# prototype.net
KiCad netlist of a schematic drawn in Altium Designer
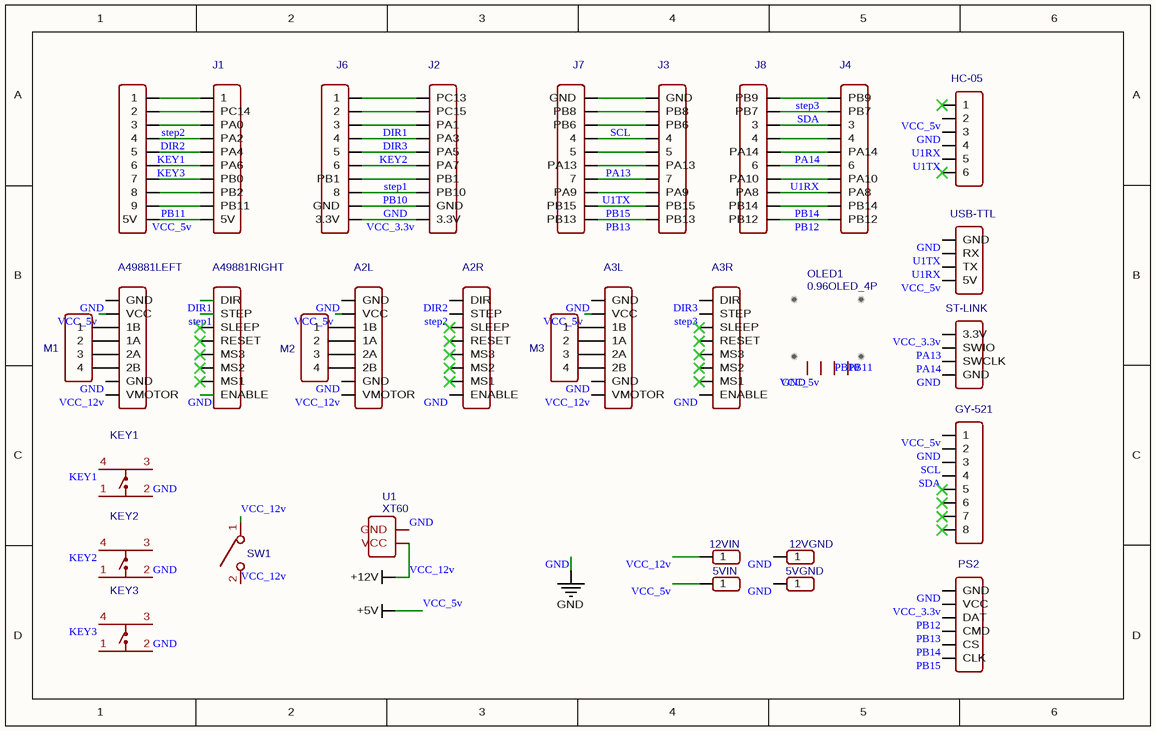
[diagram p0: prototype.schdoc]

(export (version "E")
  (design (tool "Eeschema 10.0.6"))
  (components
    (comp (ref "5VGND")
      (value "HDR-M-2.54_1x1")
      (fields (field (name "BOM_SUPPLIER PART") "C81276") (field (name "CONTRIBUTOR") "LCEDA_Lib"))
      (libsource (lib "altium-import") (part "root_0_HDR-M-2.54_1x1_"))
    )
    (comp (ref "5VIN")
      (value "HDR-M-2.54_1x1")
      (fields (field (name "BOM_SUPPLIER PART") "C81276") (field (name "CONTRIBUTOR") "LCEDA_Lib"))
      (libsource (lib "altium-import") (part "root_0_HDR-M-2.54_1x1_"))
    )
    (comp (ref "12VGND")
      (value "HDR-M-2.54_1x1")
      (fields (field (name "BOM_SUPPLIER PART") "C81276") (field (name "CONTRIBUTOR") "LCEDA_Lib"))
      (libsource (lib "altium-import") (part "root_0_HDR-M-2.54_1x1_"))
    )
    (comp (ref "12VIN")
      (value "HDR-M-2.54_1x1")
      (fields (field (name "BOM_SUPPLIER PART") "C81276") (field (name "CONTRIBUTOR") "LCEDA_Lib"))
      (libsource (lib "altium-import") (part "root_0_HDR-M-2.54_1x1_"))
    )
    (comp (ref "A2L")
      (value "HDR-M-2.54_1x8")
      (fields (field (name "BOM_SUPPLIER PART") "C190820") (field (name "CONTRIBUTOR") "LCEDA_Lib"))
      (libsource (lib "altium-import") (part "root_0_HDR-M-2.54_1x8_"))
    )
    (comp (ref "A2R")
      (value "HDR-M-2.54_1x8")
      (fields (field (name "BOM_SUPPLIER PART") "C190820") (field (name "CONTRIBUTOR") "LCEDA_Lib"))
      (libsource (lib "altium-import") (part "root_0_HDR-M-2.54_1x8_"))
    )
    (comp (ref "A3L")
      (value "HDR-M-2.54_1x8")
      (fields (field (name "BOM_SUPPLIER PART") "C190820") (field (name "CONTRIBUTOR") "LCEDA_Lib"))
      (libsource (lib "altium-import") (part "root_0_HDR-M-2.54_1x8_"))
    )
    (comp (ref "A3R")
      (value "HDR-M-2.54_1x8")
      (fields (field (name "BOM_SUPPLIER PART") "C190820") (field (name "CONTRIBUTOR") "LCEDA_Lib"))
      (libsource (lib "altium-import") (part "root_0_HDR-M-2.54_1x8_"))
    )
    (comp (ref "A49881LEFT")
      (value "HDR-M-2.54_1x8")
      (fields (field (name "BOM_SUPPLIER PART") "C190820") (field (name "CONTRIBUTOR") "LCEDA_Lib"))
      (libsource (lib "altium-import") (part "root_0_HDR-M-2.54_1x8_"))
    )
    (comp (ref "A49881RIGHT")
      (value "HDR-M-2.54_1x8")
      (fields (field (name "BOM_SUPPLIER PART") "C190820") (field (name "CONTRIBUTOR") "LCEDA_Lib"))
      (libsource (lib "altium-import") (part "root_0_HDR-M-2.54_1x8_"))
    )
    (comp (ref "GY-521")
      (value "HDR-M-2.54_1x8")
      (fields (field (name "BOM_SUPPLIER PART") "C190820") (field (name "CONTRIBUTOR") "LCEDA_Lib"))
      (libsource (lib "altium-import") (part "root_0_HDR-M-2.54_1x8_"))
    )
    (comp (ref "HC-05")
      (value "HDR-M-2.54_1x6")
      (fields (field (name "BOM_SUPPLIER PART") "C190819") (field (name "CONTRIBUTOR") "LCEDA_Lib"))
      (libsource (lib "") (part "root_2_HDR-M-2.54_1x6__1"))
    )
    (comp (ref "J1")
      (value "HDR-M-2.54_1x10")
      (fields (field (name "BOM_SUPPLIER PART") "C57369") (field (name "CONTRIBUTOR") "LCEDA_Lib"))
      (libsource (lib "altium-import") (part "root_0_HDR-M-2.54_1x10_"))
    )
    (comp (ref "J2")
      (value "HDR-M-2.54_1x10")
      (fields (field (name "BOM_SUPPLIER PART") "C57369") (field (name "CONTRIBUTOR") "LCEDA_Lib"))
      (libsource (lib "altium-import") (part "root_0_HDR-M-2.54_1x10_"))
    )
    (comp (ref "J3")
      (value "HDR-M-2.54_1x10")
      (fields (field (name "BOM_SUPPLIER PART") "C57369") (field (name "CONTRIBUTOR") "LCEDA_Lib"))
      (libsource (lib "altium-import") (part "root_0_HDR-M-2.54_1x10_"))
    )
    (comp (ref "J4")
      (value "HDR-M-2.54_1x10")
      (fields (field (name "BOM_SUPPLIER PART") "C57369") (field (name "CONTRIBUTOR") "LCEDA_Lib"))
      (libsource (lib "altium-import") (part "root_0_HDR-M-2.54_1x10_"))
    )
    (comp (ref "J5")
      (value "HDR-M-2.54_1x10")
      (fields (field (name "BOM_SUPPLIER PART") "C57369") (field (name "CONTRIBUTOR") "LCEDA_Lib"))
      (libsource (lib "altium-import") (part "root_2_HDR-M-2.54_1x10_"))
    )
    (comp (ref "J6")
      (value "HDR-M-2.54_1x10")
      (fields (field (name "BOM_SUPPLIER PART") "C57369") (field (name "CONTRIBUTOR") "LCEDA_Lib"))
      (libsource (lib "") (part "root_0_HDR-M-2.54_1x10__2"))
    )
    (comp (ref "J7")
      (value "HDR-M-2.54_1x10")
      (fields (field (name "BOM_SUPPLIER PART") "C57369") (field (name "CONTRIBUTOR") "LCEDA_Lib"))
      (libsource (lib "") (part "root_0_HDR-M-2.54_1x10__3"))
    )
    (comp (ref "J8")
      (value "HDR-M-2.54_1x10")
      (fields (field (name "BOM_SUPPLIER PART") "C57369") (field (name "CONTRIBUTOR") "LCEDA_Lib"))
      (libsource (lib "") (part "root_0_HDR-M-2.54_1x10__1"))
    )
    (comp (ref "KEY1")
      (value "KEY-6*6*9.5")
      (fields
        (field (name "BOM_SUPPLIER PART") "C22546")
        (field (name "BOM_MANUFACTURER PART") "直插轻触开关 6*6*9.5")
      )
      (libsource (lib "altium-import") (part "root_0_KEY-6*6*9.5_"))
    )
    (comp (ref "KEY2")
      (value "KEY-6*6*9.5")
      (fields
        (field (name "BOM_SUPPLIER PART") "C22546")
        (field (name "BOM_MANUFACTURER PART") "直插轻触开关 6*6*9.5")
      )
      (libsource (lib "altium-import") (part "root_0_KEY-6*6*9.5_"))
    )
    (comp (ref "KEY3")
      (value "KEY-6*6*9.5")
      (fields
        (field (name "BOM_SUPPLIER PART") "C22546")
        (field (name "BOM_MANUFACTURER PART") "直插轻触开关 6*6*9.5")
      )
      (libsource (lib "altium-import") (part "root_0_KEY-6*6*9.5_"))
    )
    (comp (ref "M1")
      (value "HDR-M-2.54_1x4")
      (fields (field (name "BOM_SUPPLIER PART") "C124378") (field (name "CONTRIBUTOR") "LCEDA_Lib"))
      (libsource (lib "") (part "root_0_HDR-M-2.54_1x4__1"))
    )
    (comp (ref "M2")
      (value "HDR-M-2.54_1x4")
      (fields (field (name "BOM_SUPPLIER PART") "C124378") (field (name "CONTRIBUTOR") "LCEDA_Lib"))
      (libsource (lib "") (part "root_0_HDR-M-2.54_1x4__1"))
    )
    (comp (ref "M3")
      (value "HDR-M-2.54_1x4")
      (fields (field (name "BOM_SUPPLIER PART") "C124378") (field (name "CONTRIBUTOR") "LCEDA_Lib"))
      (libsource (lib "") (part "root_0_HDR-M-2.54_1x4__1"))
    )
    (comp (ref "OLED1")
      (value "0.96OLED_4P")
      (fields (field (name "CONTRIBUTOR") "LCEDA_Lib"))
      (libsource (lib "altium-import") (part "root_0_0.96OLED_4P_"))
    )
    (comp (ref "PS2")
      (value "HDR-M-2.54_1x6")
      (fields (field (name "BOM_SUPPLIER PART") "C190819") (field (name "CONTRIBUTOR") "LCEDA_Lib"))
      (libsource (lib "altium-import") (part "root_2_HDR-M-2.54_1x6_"))
    )
    (comp (ref "ST-LINK")
      (value "HDR-M-2.54_1x4")
      (fields (field (name "BOM_SUPPLIER PART") "C124378") (field (name "CONTRIBUTOR") "LCEDA_Lib"))
      (libsource (lib "altium-import") (part "root_0_HDR-M-2.54_1x4_"))
    )
    (comp (ref "SW1")
      (value "小型 船型/形开关 KCD11 2档2脚 2档3脚 15*10mm 翘板开关")
      (fields
        (field (name "BOM_SUPPLIER PART") "C309064")
        (field (name "BOM_MANUFACTURER PART") "SS01-BBIWL-RP20-R")
        (field (name "CONTRIBUTOR") "CyTech")
      )
      (libsource (lib "altium-import") (part "root_1_小型 船型/形开关 KCD11 2档2脚 2档3脚 15*10mm 翘板开关_"))
    )
    (comp (ref "U1")
      (value "XT60")
      (fields (field (name "CONTRIBUTOR") "AKER"))
      (libsource (lib "altium-import") (part "root_2_XT60_"))
    )
    (comp (ref "USB-TTL")
      (value "HDR-M-2.54_1x4")
      (fields (field (name "BOM_SUPPLIER PART") "C124378") (field (name "CONTRIBUTOR") "LCEDA_Lib"))
      (libsource (lib "") (part "root_0_HDR-M-2.54_1x4__2"))
    )
  )
  (nets
    (net (code "1") (name "+5V") (class "Default")
      (node (ref "5VIN") (pin "1") (pinfunction "1_1") (pintype "passive"))
      (node (ref "A2L") (pin "2") (pinfunction "VCC_2") (pintype "passive"))
      (node (ref "A3L") (pin "2") (pinfunction "VCC_2") (pintype "passive"))
      (node (ref "A49881LEFT") (pin "2") (pinfunction "VCC_2") (pintype "passive"))
      (node (ref "GY-521") (pin "1") (pinfunction "GND_1") (pintype "passive"))
      (node (ref "HC-05") (pin "2") (pinfunction "2_2") (pintype "passive"))
      (node (ref "J1") (pin "10") (pinfunction "5V_10") (pintype "passive"))
      (node (ref "J5") (pin "10") (pinfunction "5V_10") (pintype "passive"))
      (node (ref "OLED1") (pin "2") (pinfunction "2_2") (pintype "passive"))
      (node (ref "USB-TTL") (pin "4") (pinfunction "5V_4") (pintype "passive"))
    )
    (net (code "2") (name "+12V") (class "Default")
      (node (ref "12VIN") (pin "1") (pinfunction "1_1") (pintype "passive"))
      (node (ref "A2L") (pin "8") (pinfunction "VMOTOR_8") (pintype "passive"))
      (node (ref "A3L") (pin "8") (pinfunction "VMOTOR_8") (pintype "passive"))
      (node (ref "A49881LEFT") (pin "8") (pinfunction "VMOTOR_8") (pintype "passive"))
      (node (ref "SW1") (pin "1") (pinfunction "1_1") (pintype "passive"))
      (node (ref "SW1") (pin "2") (pinfunction "2_2") (pintype "passive"))
      (node (ref "U1") (pin "1") (pinfunction "VCC_1") (pintype "passive"))
    )
    (net (code "3") (name "/DIR1") (class "Default")
      (node (ref "A49881RIGHT") (pin "1") (pinfunction "GND_1") (pintype "passive"))
      (node (ref "J2") (pin "3") (pinfunction "PA0_3") (pintype "passive"))
      (node (ref "J6") (pin "3") (pinfunction "3_3") (pintype "passive"))
    )
    (net (code "4") (name "/DIR2") (class "Default")
      (node (ref "A2R") (pin "1") (pinfunction "GND_1") (pintype "passive"))
      (node (ref "J1") (pin "4") (pinfunction "PA2_4") (pintype "passive"))
      (node (ref "J5") (pin "4") (pinfunction "4_4") (pintype "passive"))
    )
    (net (code "5") (name "/DIR3") (class "Default")
      (node (ref "A3R") (pin "1") (pinfunction "GND_1") (pintype "passive"))
      (node (ref "J2") (pin "4") (pinfunction "PA2_4") (pintype "passive"))
      (node (ref "J6") (pin "4") (pinfunction "4_4") (pintype "passive"))
    )
    (net (code "6") (name "/KEY1") (class "Default")
      (node (ref "J1") (pin "5") (pinfunction "PA4_5") (pintype "passive"))
      (node (ref "J5") (pin "5") (pinfunction "5_5") (pintype "passive"))
      (node (ref "KEY1") (pin "4") (pinfunction "4_4") (pintype "passive"))
    )
    (net (code "7") (name "/KEY2") (class "Default")
      (node (ref "J2") (pin "5") (pinfunction "PA4_5") (pintype "passive"))
      (node (ref "J6") (pin "5") (pinfunction "5_5") (pintype "passive"))
      (node (ref "KEY2") (pin "4") (pinfunction "4_4") (pintype "passive"))
    )
    (net (code "8") (name "/KEY3") (class "Default")
      (node (ref "J1") (pin "6") (pinfunction "PA6_6") (pintype "passive"))
      (node (ref "J5") (pin "6") (pinfunction "6_6") (pintype "passive"))
      (node (ref "KEY3") (pin "4") (pinfunction "4_4") (pintype "passive"))
    )
    (net (code "9") (name "/PA13") (class "Default")
      (node (ref "J3") (pin "6") (pinfunction "PA6_6") (pintype "passive"))
      (node (ref "J7") (pin "6") (pinfunction "PA13_6") (pintype "passive"))
      (node (ref "ST-LINK") (pin "2") (pinfunction "SWIO_2") (pintype "passive"))
    )
    (net (code "10") (name "/PA14") (class "Default")
      (node (ref "J4") (pin "5") (pinfunction "PA4_5") (pintype "passive"))
      (node (ref "J8") (pin "5") (pinfunction "PA14_5") (pintype "passive"))
      (node (ref "ST-LINK") (pin "3") (pinfunction "SWCLK_3") (pintype "passive"))
    )
    (net (code "11") (name "/PB10") (class "Default")
      (node (ref "J2") (pin "8") (pinfunction "PB2_8") (pintype "passive"))
      (node (ref "J6") (pin "8") (pinfunction "8_8") (pintype "passive"))
      (node (ref "OLED1") (pin "3") (pinfunction "3_3") (pintype "passive"))
    )
    (net (code "12") (name "/PB11") (class "Default")
      (node (ref "J1") (pin "9") (pinfunction "PB11_9") (pintype "passive"))
      (node (ref "J5") (pin "9") (pinfunction "9_9") (pintype "passive"))
      (node (ref "OLED1") (pin "4") (pinfunction "4_4") (pintype "passive"))
    )
    (net (code "13") (name "/PB12") (class "Default")
      (node (ref "J4") (pin "10") (pinfunction "5V_10") (pintype "passive"))
      (node (ref "J8") (pin "10") (pinfunction "PB12_10") (pintype "passive"))
      (node (ref "PS2") (pin "4") (pinfunction "DAT_4") (pintype "passive"))
    )
    (net (code "14") (name "/PB13") (class "Default")
      (node (ref "J3") (pin "10") (pinfunction "5V_10") (pintype "passive"))
      (node (ref "J7") (pin "10") (pinfunction "PB13_10") (pintype "passive"))
      (node (ref "PS2") (pin "3") (pinfunction "CMD_3") (pintype "passive"))
    )
    (net (code "15") (name "/PB14") (class "Default")
      (node (ref "J4") (pin "9") (pinfunction "PB11_9") (pintype "passive"))
      (node (ref "J8") (pin "9") (pinfunction "PB14_9") (pintype "passive"))
      (node (ref "PS2") (pin "2") (pinfunction "CS_2") (pintype "passive"))
    )
    (net (code "16") (name "/PB15") (class "Default")
      (node (ref "J3") (pin "9") (pinfunction "PB11_9") (pintype "passive"))
      (node (ref "J7") (pin "9") (pinfunction "PB15_9") (pintype "passive"))
      (node (ref "PS2") (pin "1") (pinfunction "CLK_1") (pintype "passive"))
    )
    (net (code "17") (name "/SCL") (class "Default")
      (node (ref "GY-521") (pin "3") (pinfunction "1B_3") (pintype "passive"))
      (node (ref "J3") (pin "3") (pinfunction "PA0_3") (pintype "passive"))
      (node (ref "J7") (pin "3") (pinfunction "PB6_3") (pintype "passive"))
    )
    (net (code "18") (name "/SDA") (class "Default")
      (node (ref "GY-521") (pin "4") (pinfunction "1A_4") (pintype "passive"))
      (node (ref "J4") (pin "2") (pinfunction "PC14_2") (pintype "passive"))
      (node (ref "J8") (pin "2") (pinfunction "PB7_2") (pintype "passive"))
    )
    (net (code "19") (name "/U1RX") (class "Default")
      (node (ref "HC-05") (pin "4") (pinfunction "4_4") (pintype "passive"))
      (node (ref "J4") (pin "7") (pinfunction "PB0_7") (pintype "passive"))
      (node (ref "J8") (pin "7") (pinfunction "PA10_7") (pintype "passive"))
      (node (ref "USB-TTL") (pin "3") (pinfunction "TX_3") (pintype "passive"))
    )
    (net (code "20") (name "/U1TX") (class "Default")
      (node (ref "HC-05") (pin "5") (pinfunction "5_5") (pintype "passive"))
      (node (ref "J3") (pin "8") (pinfunction "PB2_8") (pintype "passive"))
      (node (ref "J7") (pin "8") (pinfunction "PA9_8") (pintype "passive"))
      (node (ref "USB-TTL") (pin "2") (pinfunction "RX_2") (pintype "passive"))
    )
    (net (code "21") (name "/VCC_3.3v") (class "Default")
      (node (ref "J2") (pin "10") (pinfunction "5V_10") (pintype "passive"))
      (node (ref "J6") (pin "10") (pinfunction "3.3V_10") (pintype "passive"))
      (node (ref "PS2") (pin "5") (pinfunction "VCC_5") (pintype "passive"))
      (node (ref "ST-LINK") (pin "1") (pinfunction "3.3V_1") (pintype "passive"))
    )
    (net (code "22") (name "/step1") (class "Default")
      (node (ref "A49881RIGHT") (pin "2") (pinfunction "VCC_2") (pintype "passive"))
      (node (ref "J2") (pin "7") (pinfunction "PB0_7") (pintype "passive"))
      (node (ref "J6") (pin "7") (pinfunction "PB1_7") (pintype "passive"))
    )
    (net (code "23") (name "/step2") (class "Default")
      (node (ref "A2R") (pin "2") (pinfunction "VCC_2") (pintype "passive"))
      (node (ref "J1") (pin "3") (pinfunction "PA0_3") (pintype "passive"))
      (node (ref "J5") (pin "3") (pinfunction "3_3") (pintype "passive"))
    )
    (net (code "24") (name "/step3") (class "Default")
      (node (ref "A3R") (pin "2") (pinfunction "VCC_2") (pintype "passive"))
      (node (ref "J4") (pin "1") (pinfunction "1_1") (pintype "passive"))
      (node (ref "J8") (pin "1") (pinfunction "PB9_1") (pintype "passive"))
    )
    (net (code "25") (name "GND") (class "Default")
      (node (ref "12VGND") (pin "1") (pinfunction "1_1") (pintype "passive"))
      (node (ref "5VGND") (pin "1") (pinfunction "1_1") (pintype "passive"))
      (node (ref "A2L") (pin "1") (pinfunction "GND_1") (pintype "passive"))
      (node (ref "A2L") (pin "7") (pinfunction "GND_7") (pintype "passive"))
      (node (ref "A2R") (pin "8") (pinfunction "VMOTOR_8") (pintype "passive"))
      (node (ref "A3L") (pin "1") (pinfunction "GND_1") (pintype "passive"))
      (node (ref "A3L") (pin "7") (pinfunction "GND_7") (pintype "passive"))
      (node (ref "A3R") (pin "8") (pinfunction "VMOTOR_8") (pintype "passive"))
      (node (ref "A49881LEFT") (pin "1") (pinfunction "GND_1") (pintype "passive"))
      (node (ref "A49881LEFT") (pin "7") (pinfunction "GND_7") (pintype "passive"))
      (node (ref "A49881RIGHT") (pin "8") (pinfunction "VMOTOR_8") (pintype "passive"))
      (node (ref "GY-521") (pin "2") (pinfunction "VCC_2") (pintype "passive"))
      (node (ref "HC-05") (pin "3") (pinfunction "3_3") (pintype "passive"))
      (node (ref "J2") (pin "9") (pinfunction "PB11_9") (pintype "passive"))
      (node (ref "J6") (pin "9") (pinfunction "GND_9") (pintype "passive"))
      (node (ref "KEY1") (pin "2") (pinfunction "2_2") (pintype "passive"))
      (node (ref "KEY2") (pin "2") (pinfunction "2_2") (pintype "passive"))
      (node (ref "KEY3") (pin "2") (pinfunction "2_2") (pintype "passive"))
      (node (ref "OLED1") (pin "1") (pinfunction "1_1") (pintype "passive"))
      (node (ref "PS2") (pin "6") (pinfunction "GND_6") (pintype "passive"))
      (node (ref "ST-LINK") (pin "4") (pinfunction "GND_4") (pintype "passive"))
      (node (ref "U1") (pin "2") (pinfunction "GND_2") (pintype "passive"))
      (node (ref "USB-TTL") (pin "1") (pinfunction "GND_1") (pintype "passive"))
    )
    (net (code "26") (name "Net-(A2L-1A)") (class "Default")
      (node (ref "A2L") (pin "4") (pinfunction "1A_4") (pintype "passive"))
      (node (ref "M2") (pin "2") (pinfunction "2_2") (pintype "passive"))
    )
    (net (code "27") (name "Net-(A2L-1B)") (class "Default")
      (node (ref "A2L") (pin "3") (pinfunction "1B_3") (pintype "passive"))
      (node (ref "M2") (pin "1") (pinfunction "1_1") (pintype "passive"))
    )
    (net (code "28") (name "Net-(A2L-2A)") (class "Default")
      (node (ref "A2L") (pin "5") (pinfunction "2A_5") (pintype "passive"))
      (node (ref "M2") (pin "3") (pinfunction "3_3") (pintype "passive"))
    )
    (net (code "29") (name "Net-(A2L-2B)") (class "Default")
      (node (ref "A2L") (pin "6") (pinfunction "2B_6") (pintype "passive"))
      (node (ref "M2") (pin "4") (pinfunction "4_4") (pintype "passive"))
    )
    (net (code "30") (name "Net-(A3L-1A)") (class "Default")
      (node (ref "A3L") (pin "4") (pinfunction "1A_4") (pintype "passive"))
      (node (ref "M3") (pin "2") (pinfunction "2_2") (pintype "passive"))
    )
    (net (code "31") (name "Net-(A3L-1B)") (class "Default")
      (node (ref "A3L") (pin "3") (pinfunction "1B_3") (pintype "passive"))
      (node (ref "M3") (pin "1") (pinfunction "1_1") (pintype "passive"))
    )
    (net (code "32") (name "Net-(A3L-2A)") (class "Default")
      (node (ref "A3L") (pin "5") (pinfunction "2A_5") (pintype "passive"))
      (node (ref "M3") (pin "3") (pinfunction "3_3") (pintype "passive"))
    )
    (net (code "33") (name "Net-(A3L-2B)") (class "Default")
      (node (ref "A3L") (pin "6") (pinfunction "2B_6") (pintype "passive"))
      (node (ref "M3") (pin "4") (pinfunction "4_4") (pintype "passive"))
    )
    (net (code "34") (name "Net-(A49881LEFT-1A)") (class "Default")
      (node (ref "A49881LEFT") (pin "4") (pinfunction "1A_4") (pintype "passive"))
      (node (ref "M1") (pin "2") (pinfunction "2_2") (pintype "passive"))
    )
    (net (code "35") (name "Net-(A49881LEFT-1B)") (class "Default")
      (node (ref "A49881LEFT") (pin "3") (pinfunction "1B_3") (pintype "passive"))
      (node (ref "M1") (pin "1") (pinfunction "1_1") (pintype "passive"))
    )
    (net (code "36") (name "Net-(A49881LEFT-2A)") (class "Default")
      (node (ref "A49881LEFT") (pin "5") (pinfunction "2A_5") (pintype "passive"))
      (node (ref "M1") (pin "3") (pinfunction "3_3") (pintype "passive"))
    )
    (net (code "37") (name "Net-(A49881LEFT-2B)") (class "Default")
      (node (ref "A49881LEFT") (pin "6") (pinfunction "2B_6") (pintype "passive"))
      (node (ref "M1") (pin "4") (pinfunction "4_4") (pintype "passive"))
    )
    (net (code "38") (name "Net-(J1-PB0)") (class "Default")
      (node (ref "J1") (pin "7") (pinfunction "PB0_7") (pintype "passive"))
      (node (ref "J5") (pin "7") (pinfunction "7_7") (pintype "passive"))
    )
    (net (code "39") (name "Net-(J1-PB2)") (class "Default")
      (node (ref "J1") (pin "8") (pinfunction "PB2_8") (pintype "passive"))
      (node (ref "J5") (pin "8") (pinfunction "8_8") (pintype "passive"))
    )
    (net (code "40") (name "Net-(J1-PC14)") (class "Default")
      (node (ref "J1") (pin "2") (pinfunction "PC14_2") (pintype "passive"))
      (node (ref "J5") (pin "2") (pinfunction "2_2") (pintype "passive"))
    )
    (net (code "41") (name "Net-(J1-Pad1)") (class "Default")
      (node (ref "J1") (pin "1") (pinfunction "1_1") (pintype "passive"))
      (node (ref "J5") (pin "1") (pinfunction "1_1") (pintype "passive"))
    )
    (net (code "42") (name "Net-(J2-PA6)") (class "Default")
      (node (ref "J2") (pin "6") (pinfunction "PA6_6") (pintype "passive"))
      (node (ref "J6") (pin "6") (pinfunction "6_6") (pintype "passive"))
    )
    (net (code "43") (name "Net-(J2-PC14)") (class "Default")
      (node (ref "J2") (pin "2") (pinfunction "PC14_2") (pintype "passive"))
      (node (ref "J6") (pin "2") (pinfunction "2_2") (pintype "passive"))
    )
    (net (code "44") (name "Net-(J2-Pad1)") (class "Default")
      (node (ref "J2") (pin "1") (pinfunction "1_1") (pintype "passive"))
      (node (ref "J6") (pin "1") (pinfunction "1_1") (pintype "passive"))
    )
    (net (code "45") (name "Net-(J3-PA2)") (class "Default")
      (node (ref "J3") (pin "4") (pinfunction "PA2_4") (pintype "passive"))
      (node (ref "J7") (pin "4") (pinfunction "4_4") (pintype "passive"))
    )
    (net (code "46") (name "Net-(J3-PA4)") (class "Default")
      (node (ref "J3") (pin "5") (pinfunction "PA4_5") (pintype "passive"))
      (node (ref "J7") (pin "5") (pinfunction "5_5") (pintype "passive"))
    )
    (net (code "47") (name "Net-(J3-PB0)") (class "Default")
      (node (ref "J3") (pin "7") (pinfunction "PB0_7") (pintype "passive"))
      (node (ref "J7") (pin "7") (pinfunction "7_7") (pintype "passive"))
    )
    (net (code "48") (name "Net-(J3-PC14)") (class "Default")
      (node (ref "J3") (pin "2") (pinfunction "PC14_2") (pintype "passive"))
      (node (ref "J7") (pin "2") (pinfunction "PB8_2") (pintype "passive"))
    )
    (net (code "49") (name "Net-(J4-PA0)") (class "Default")
      (node (ref "J4") (pin "3") (pinfunction "PA0_3") (pintype "passive"))
      (node (ref "J8") (pin "3") (pinfunction "3_3") (pintype "passive"))
    )
    (net (code "50") (name "Net-(J4-PA2)") (class "Default")
      (node (ref "J4") (pin "4") (pinfunction "PA2_4") (pintype "passive"))
      (node (ref "J8") (pin "4") (pinfunction "4_4") (pintype "passive"))
    )
    (net (code "51") (name "Net-(J4-PA6)") (class "Default")
      (node (ref "J4") (pin "6") (pinfunction "PA6_6") (pintype "passive"))
      (node (ref "J8") (pin "6") (pinfunction "6_6") (pintype "passive"))
    )
    (net (code "52") (name "Net-(J4-PB2)") (class "Default")
      (node (ref "J4") (pin "8") (pinfunction "PB2_8") (pintype "passive"))
      (node (ref "J8") (pin "8") (pinfunction "PA8_8") (pintype "passive"))
    )
    (net (code "53") (name "Net-(J7-GND)") (class "Default")
      (node (ref "J3") (pin "1") (pinfunction "1_1") (pintype "passive"))
      (node (ref "J7") (pin "1") (pinfunction "GND_1") (pintype "passive"))
    )
    (net (code "54") (name "unconnected-(A2R-1A-Pad4)") (class "Default")
      (node (ref "A2R") (pin "4") (pinfunction "1A_4") (pintype "passive+no_connect"))
    )
    (net (code "55") (name "unconnected-(A2R-1B-Pad3)") (class "Default")
      (node (ref "A2R") (pin "3") (pinfunction "1B_3") (pintype "passive+no_connect"))
    )
    (net (code "56") (name "unconnected-(A2R-2A-Pad5)") (class "Default")
      (node (ref "A2R") (pin "5") (pinfunction "2A_5") (pintype "passive+no_connect"))
    )
    (net (code "57") (name "unconnected-(A2R-2B-Pad6)") (class "Default")
      (node (ref "A2R") (pin "6") (pinfunction "2B_6") (pintype "passive+no_connect"))
    )
    (net (code "58") (name "unconnected-(A2R-GND-Pad7)") (class "Default")
      (node (ref "A2R") (pin "7") (pinfunction "GND_7") (pintype "passive+no_connect"))
    )
    (net (code "59") (name "unconnected-(A3R-1A-Pad4)") (class "Default")
      (node (ref "A3R") (pin "4") (pinfunction "1A_4") (pintype "passive+no_connect"))
    )
    (net (code "60") (name "unconnected-(A3R-1B-Pad3)") (class "Default")
      (node (ref "A3R") (pin "3") (pinfunction "1B_3") (pintype "passive+no_connect"))
    )
    (net (code "61") (name "unconnected-(A3R-2A-Pad5)") (class "Default")
      (node (ref "A3R") (pin "5") (pinfunction "2A_5") (pintype "passive+no_connect"))
    )
    (net (code "62") (name "unconnected-(A3R-2B-Pad6)") (class "Default")
      (node (ref "A3R") (pin "6") (pinfunction "2B_6") (pintype "passive+no_connect"))
    )
    (net (code "63") (name "unconnected-(A3R-GND-Pad7)") (class "Default")
      (node (ref "A3R") (pin "7") (pinfunction "GND_7") (pintype "passive+no_connect"))
    )
    (net (code "64") (name "unconnected-(A49881RIGHT-1A-Pad4)") (class "Default")
      (node (ref "A49881RIGHT") (pin "4") (pinfunction "1A_4") (pintype "passive+no_connect"))
    )
    (net (code "65") (name "unconnected-(A49881RIGHT-1B-Pad3)") (class "Default")
      (node (ref "A49881RIGHT") (pin "3") (pinfunction "1B_3") (pintype "passive+no_connect"))
    )
    (net (code "66") (name "unconnected-(A49881RIGHT-2A-Pad5)") (class "Default")
      (node (ref "A49881RIGHT") (pin "5") (pinfunction "2A_5") (pintype "passive+no_connect"))
    )
    (net (code "67") (name "unconnected-(A49881RIGHT-2B-Pad6)") (class "Default")
      (node (ref "A49881RIGHT") (pin "6") (pinfunction "2B_6") (pintype "passive+no_connect"))
    )
    (net (code "68") (name "unconnected-(A49881RIGHT-GND-Pad7)") (class "Default")
      (node (ref "A49881RIGHT") (pin "7") (pinfunction "GND_7") (pintype "passive+no_connect"))
    )
    (net (code "69") (name "unconnected-(GY-521-2A-Pad5)") (class "Default")
      (node (ref "GY-521") (pin "5") (pinfunction "2A_5") (pintype "passive+no_connect"))
    )
    (net (code "70") (name "unconnected-(GY-521-2B-Pad6)") (class "Default")
      (node (ref "GY-521") (pin "6") (pinfunction "2B_6") (pintype "passive+no_connect"))
    )
    (net (code "71") (name "unconnected-(GY-521-GND-Pad7)") (class "Default")
      (node (ref "GY-521") (pin "7") (pinfunction "GND_7") (pintype "passive+no_connect"))
    )
    (net (code "72") (name "unconnected-(GY-521-VMOTOR-Pad8)") (class "Default")
      (node (ref "GY-521") (pin "8") (pinfunction "VMOTOR_8") (pintype "passive+no_connect"))
    )
    (net (code "73") (name "unconnected-(HC-05-Pad1)") (class "Default")
      (node (ref "HC-05") (pin "1") (pinfunction "1_1") (pintype "passive+no_connect"))
    )
    (net (code "74") (name "unconnected-(HC-05-Pad6)") (class "Default")
      (node (ref "HC-05") (pin "6") (pinfunction "6_6") (pintype "passive+no_connect"))
    )
    (net (code "75") (name "unconnected-(KEY1-Pad1)") (class "Default")
      (node (ref "KEY1") (pin "1") (pinfunction "1_1") (pintype "passive"))
    )
    (net (code "76") (name "unconnected-(KEY1-Pad3)") (class "Default")
      (node (ref "KEY1") (pin "3") (pinfunction "3_3") (pintype "passive"))
    )
    (net (code "77") (name "unconnected-(KEY2-Pad1)") (class "Default")
      (node (ref "KEY2") (pin "1") (pinfunction "1_1") (pintype "passive"))
    )
    (net (code "78") (name "unconnected-(KEY2-Pad3)") (class "Default")
      (node (ref "KEY2") (pin "3") (pinfunction "3_3") (pintype "passive"))
    )
    (net (code "79") (name "unconnected-(KEY3-Pad1)") (class "Default")
      (node (ref "KEY3") (pin "1") (pinfunction "1_1") (pintype "passive"))
    )
    (net (code "80") (name "unconnected-(KEY3-Pad3)") (class "Default")
      (node (ref "KEY3") (pin "3") (pinfunction "3_3") (pintype "passive"))
    )
  )
)
